# EIS_Sensoren.net
KiCad netlist of a schematic drawn in Altium Designer
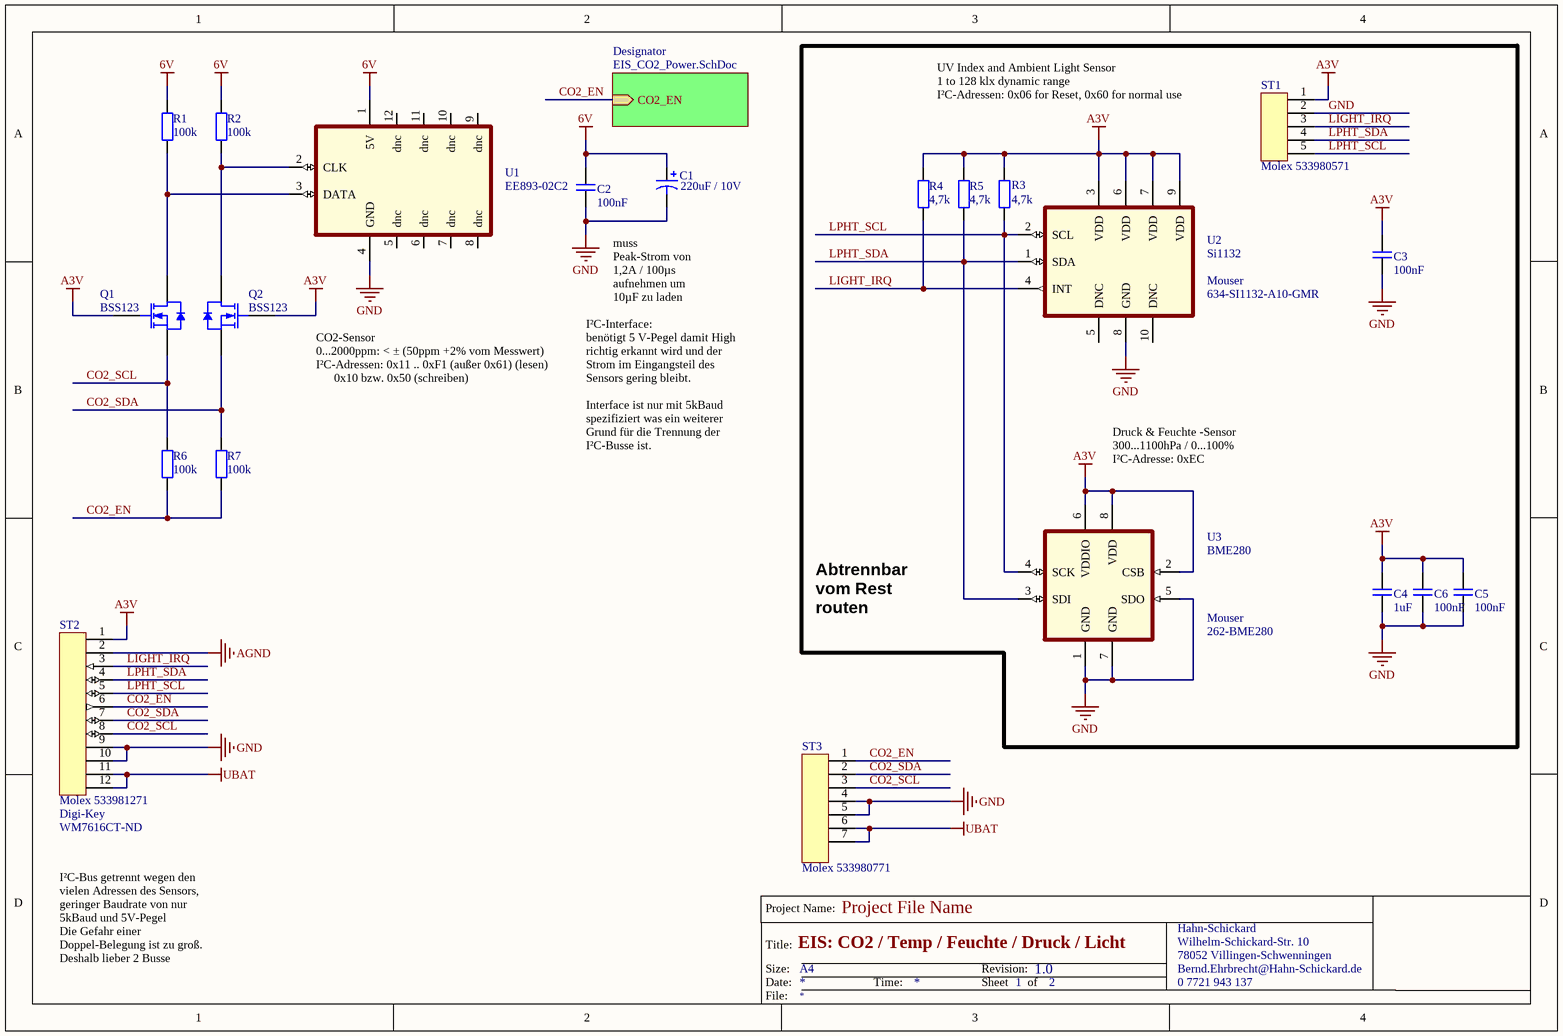
[diagram p0: EIS_Sensoren.SchDoc]

(export (version "E")
  (design (tool "Eeschema 10.0.6"))
  (components
    (comp (ref "C1")
      (value "220uF / 10V")
      (footprint "D")
      (description "Polarized Capacitor (Surface Mount)")
      (fields (field (name "PUBLISHER") "Altium Limited"))
      (libsource (lib "Miscellaneous Devices") (part "Cap Pol3"))
    )
    (comp (ref "C2")
      (value "100nF")
      (footprint "CAPC1608N")
      (libsource (lib "My_Schlib_6_18") (part "Kondensator SMD Keramik"))
    )
    (comp (ref "C3")
      (value "100nF")
      (footprint "CAPC1608N")
      (libsource (lib "My_Schlib_6_18") (part "Kondensator SMD Keramik"))
    )
    (comp (ref "C4")
      (value "1uF")
      (footprint "CAPC3216N")
      (libsource (lib "My_Schlib_6_18") (part "Kondensator SMD Keramik"))
    )
    (comp (ref "C5")
      (value "100nF")
      (footprint "CAPC1608N")
      (libsource (lib "My_Schlib_6_18") (part "Kondensator SMD Keramik"))
    )
    (comp (ref "C6")
      (value "100nF")
      (footprint "CAPC1608N")
      (libsource (lib "My_Schlib_6_18") (part "Kondensator SMD Keramik"))
    )
    (comp (ref "Q1")
      (value "BSS123")
      (footprint "SOT23_N")
      (description "N-channel Enhancement Mode Vertical D-MOSFET")
      (fields (field (name "PUBLISHER") "Altium Limited"))
      (libsource (lib "Philips Discrete MOSFET - Low Power") (part "BSS123"))
    )
    (comp (ref "Q2")
      (value "BSS123")
      (footprint "SOT23_N")
      (description "N-channel Enhancement Mode Vertical D-MOSFET")
      (fields (field (name "PUBLISHER") "Altium Limited"))
      (libsource (lib "Philips Discrete MOSFET - Low Power") (part "BSS123"))
    )
    (comp (ref "R1")
      (value "100k")
      (footprint "RESC1608N")
      (description "RESC1608 (R0603)")
      (fields (field (name "PUBLISHER") "HSG Jürgen Merz"))
      (libsource (lib "MetaSensClampOn_BT") (part "RESC1608 (R0603)"))
    )
    (comp (ref "R2")
      (value "100k")
      (footprint "RESC1608N")
      (description "RESC1608 (R0603)")
      (fields (field (name "PUBLISHER") "HSG Jürgen Merz"))
      (libsource (lib "MetaSensClampOn_BT") (part "RESC1608 (R0603)"))
    )
    (comp (ref "R3")
      (value "4,7k")
      (footprint "RESC1608N")
      (description "RESC1608 (R0603)")
      (fields (field (name "PUBLISHER") "HSG Jürgen Merz"))
      (libsource (lib "MetaSensClampOn_BT") (part "RESC1608 (R0603)"))
    )
    (comp (ref "R4")
      (value "4,7k")
      (footprint "RESC1608N")
      (description "RESC1608 (R0603)")
      (fields (field (name "PUBLISHER") "HSG Jürgen Merz"))
      (libsource (lib "MetaSensClampOn_BT") (part "RESC1608 (R0603)"))
    )
    (comp (ref "R5")
      (value "4,7k")
      (footprint "RESC1608N")
      (description "RESC1608 (R0603)")
      (fields (field (name "PUBLISHER") "HSG Jürgen Merz"))
      (libsource (lib "MetaSensClampOn_BT") (part "RESC1608 (R0603)"))
    )
    (comp (ref "R6")
      (value "100k")
      (footprint "RESC1608N")
      (description "RESC1608 (R0603)")
      (fields (field (name "PUBLISHER") "HSG Jürgen Merz"))
      (libsource (lib "MetaSensClampOn_BT") (part "RESC1608 (R0603)"))
    )
    (comp (ref "R7")
      (value "100k")
      (footprint "RESC1608N")
      (description "RESC1608 (R0603)")
      (fields (field (name "PUBLISHER") "HSG Jürgen Merz"))
      (libsource (lib "MetaSensClampOn_BT") (part "RESC1608 (R0603)"))
    )
    (comp (ref "ST1")
      (value "Molex 533980571")
      (footprint "Molex 533980571")
      (description "MOLEX - 53398-0571 - STIFTLEISTE, SMT, 1.25MM, 5POL")
      (libsource (lib "JM_Elektromechanik") (part "Molex 533980571"))
    )
    (comp (ref "ST2")
      (value "Molex 533981271")
      (footprint "Molex 533981271")
      (description "Molex Pico 12Pol Blade SMD gerade 533980871")
      (fields (field (name "SUPPLIER 1") "Digi-Key") (field (name "SUPPLIER PART NUMBER 1") "WM7616CT-ND"))
      (libsource (lib "JM_Elektromechanik") (part "Molex 533981271"))
    )
    (comp (ref "ST3")
      (value "Molex 533980771")
      (footprint "Molex 533980771")
      (description "Molex Pico 7Pol Blade SMD gerade 533980771")
      (libsource (lib "JM_Elektromechanik") (part "Molex 533980771"))
    )
    (comp (ref "U1")
      (value "EE893-02C2")
      (footprint "EE893")
      (description "CO2-Sensor; I²C-Interface,")
      (libsource (lib "Eis_Lib") (part "EE893-02C2"))
    )
    (comp (ref "U2")
      (value "Si1132")
      (footprint "Si1132")
      (description "UV INDEX AND AMBIENT LIGHT SENSOR IC WITH I2C INTERFACE, QFN 2x2mm")
      (fields
        (field (name "SUPPLIER 1") "Mouser")
        (field (name "SUPPLIER PART NUMBER 1") "634-SI1132-A10-GMR")
      )
      (libsource (lib "Eis_Lib") (part "Si1132"))
    )
    (comp (ref "U3")
      (value "BME280")
      (footprint "BME280")
      (description "Bosch, Druck & Feuchte-Sensor, I2C / SPI")
      (fields (field (name "SUPPLIER 1") "Mouser") (field (name "SUPPLIER PART NUMBER 1") "262-BME280"))
      (libsource (lib "Eis_Lib") (part "BME280"))
    )
  )
  (nets
    (net (code "1") (name "/CO2_EN") (class "Default")
      (node (ref "R6") (pin "1") (pinfunction "1_1") (pintype "passive"))
      (node (ref "R7") (pin "1") (pinfunction "1_1") (pintype "passive"))
      (node (ref "ST2") (pin "6") (pinfunction "6_6") (pintype "output"))
      (node (ref "ST3") (pin "1") (pinfunction "1_1") (pintype "passive"))
    )
    (net (code "2") (name "/CO2_SCL") (class "Default")
      (node (ref "Q1") (pin "2") (pinfunction "S_2") (pintype "passive"))
      (node (ref "R6") (pin "2") (pinfunction "2_2") (pintype "passive"))
      (node (ref "ST2") (pin "8") (pinfunction "8_8") (pintype "bidirectional"))
      (node (ref "ST3") (pin "3") (pinfunction "3_3") (pintype "passive"))
    )
    (net (code "3") (name "/CO2_SDA") (class "Default")
      (node (ref "Q2") (pin "2") (pinfunction "S_2") (pintype "passive"))
      (node (ref "R7") (pin "2") (pinfunction "2_2") (pintype "passive"))
      (node (ref "ST2") (pin "7") (pinfunction "7_7") (pintype "bidirectional"))
      (node (ref "ST3") (pin "2") (pinfunction "2_2") (pintype "passive"))
    )
    (net (code "4") (name "/LIGHT_IRQ") (class "Default")
      (node (ref "R4") (pin "1") (pinfunction "1_1") (pintype "passive"))
      (node (ref "ST1") (pin "3") (pinfunction "3_3") (pintype "passive"))
      (node (ref "ST2") (pin "3") (pinfunction "3_3") (pintype "input"))
      (node (ref "U2") (pin "4") (pinfunction "INT_4") (pintype "output"))
    )
    (net (code "5") (name "/LPHT_SCL") (class "Default")
      (node (ref "R3") (pin "1") (pinfunction "1_1") (pintype "passive"))
      (node (ref "ST1") (pin "5") (pinfunction "5_5") (pintype "passive"))
      (node (ref "ST2") (pin "5") (pinfunction "5_5") (pintype "bidirectional"))
      (node (ref "U2") (pin "2") (pinfunction "SCL_2") (pintype "bidirectional"))
      (node (ref "U3") (pin "4") (pinfunction "SCK_4") (pintype "bidirectional"))
    )
    (net (code "6") (name "/LPHT_SDA") (class "Default")
      (node (ref "R5") (pin "1") (pinfunction "1_1") (pintype "passive"))
      (node (ref "ST1") (pin "4") (pinfunction "4_4") (pintype "passive"))
      (node (ref "ST2") (pin "4") (pinfunction "4_4") (pintype "bidirectional"))
      (node (ref "U2") (pin "1") (pinfunction "SDA_1") (pintype "bidirectional"))
      (node (ref "U3") (pin "3") (pinfunction "SDI_3") (pintype "bidirectional"))
    )
    (net (code "7") (name "6V") (class "Default")
      (node (ref "C1") (pin "1") (pinfunction "1_1") (pintype "passive"))
      (node (ref "C2") (pin "1") (pinfunction "1_1") (pintype "passive"))
      (node (ref "R1") (pin "2") (pinfunction "2_2") (pintype "passive"))
      (node (ref "R2") (pin "2") (pinfunction "2_2") (pintype "passive"))
      (node (ref "U1") (pin "1") (pinfunction "5V_1") (pintype "power_in"))
    )
    (net (code "8") (name "A3V") (class "Default")
      (node (ref "C3") (pin "1") (pinfunction "1_1") (pintype "passive"))
      (node (ref "C4") (pin "1") (pinfunction "1_1") (pintype "passive"))
      (node (ref "C5") (pin "1") (pinfunction "1_1") (pintype "passive"))
      (node (ref "C6") (pin "1") (pinfunction "1_1") (pintype "passive"))
      (node (ref "Q1") (pin "1") (pinfunction "G_1") (pintype "passive"))
      (node (ref "Q2") (pin "1") (pinfunction "G_1") (pintype "passive"))
      (node (ref "R3") (pin "2") (pinfunction "2_2") (pintype "passive"))
      (node (ref "R4") (pin "2") (pinfunction "2_2") (pintype "passive"))
      (node (ref "R5") (pin "2") (pinfunction "2_2") (pintype "passive"))
      (node (ref "ST1") (pin "1") (pinfunction "1_1") (pintype "passive"))
      (node (ref "ST2") (pin "1") (pinfunction "1_1") (pintype "passive"))
      (node (ref "U2") (pin "3") (pinfunction "VDD_3") (pintype "power_in"))
      (node (ref "U2") (pin "6") (pinfunction "VDD_6") (pintype "power_in"))
      (node (ref "U2") (pin "7") (pinfunction "VDD_7") (pintype "power_in"))
      (node (ref "U2") (pin "9") (pinfunction "VDD_9") (pintype "power_in"))
      (node (ref "U3") (pin "2") (pinfunction "CSB_2") (pintype "input"))
      (node (ref "U3") (pin "6") (pinfunction "VDDIO_6") (pintype "power_in"))
      (node (ref "U3") (pin "8") (pinfunction "VDD_8") (pintype "power_in"))
    )
    (net (code "9") (name "AGND") (class "Default")
      (node (ref "ST2") (pin "2") (pinfunction "2_2") (pintype "passive"))
    )
    (net (code "10") (name "GND") (class "Default")
      (node (ref "C1") (pin "2") (pinfunction "2_2") (pintype "passive"))
      (node (ref "C2") (pin "2") (pinfunction "2_2") (pintype "passive"))
      (node (ref "C3") (pin "2") (pinfunction "2_2") (pintype "passive"))
      (node (ref "C4") (pin "2") (pinfunction "2_2") (pintype "passive"))
      (node (ref "C5") (pin "2") (pinfunction "2_2") (pintype "passive"))
      (node (ref "C6") (pin "2") (pinfunction "2_2") (pintype "passive"))
      (node (ref "ST1") (pin "2") (pinfunction "2_2") (pintype "passive"))
      (node (ref "ST2") (pin "10") (pinfunction "10_10") (pintype "passive"))
      (node (ref "ST2") (pin "9") (pinfunction "9_9") (pintype "passive"))
      (node (ref "ST3") (pin "4") (pinfunction "4_4") (pintype "passive"))
      (node (ref "ST3") (pin "5") (pinfunction "5_5") (pintype "passive"))
      (node (ref "U1") (pin "4") (pinfunction "GND_4") (pintype "power_in"))
      (node (ref "U2") (pin "8") (pinfunction "GND_8") (pintype "power_in"))
      (node (ref "U3") (pin "1") (pinfunction "GND_1") (pintype "power_in"))
      (node (ref "U3") (pin "5") (pinfunction "SDO_5") (pintype "input"))
      (node (ref "U3") (pin "7") (pinfunction "GND_7") (pintype "power_in"))
    )
    (net (code "11") (name "Net-(Q1-D)") (class "Default")
      (node (ref "Q1") (pin "3") (pinfunction "D_3") (pintype "passive"))
      (node (ref "R1") (pin "1") (pinfunction "1_1") (pintype "passive"))
      (node (ref "U1") (pin "3") (pinfunction "DATA_3") (pintype "bidirectional"))
    )
    (net (code "12") (name "Net-(Q2-D)") (class "Default")
      (node (ref "Q2") (pin "3") (pinfunction "D_3") (pintype "passive"))
      (node (ref "R2") (pin "1") (pinfunction "1_1") (pintype "passive"))
      (node (ref "U1") (pin "2") (pinfunction "CLK_2") (pintype "bidirectional"))
    )
    (net (code "13") (name "UBAT") (class "Default")
      (node (ref "ST2") (pin "11") (pinfunction "11_11") (pintype "passive"))
      (node (ref "ST2") (pin "12") (pinfunction "12_12") (pintype "passive"))
      (node (ref "ST3") (pin "6") (pinfunction "6_6") (pintype "passive"))
      (node (ref "ST3") (pin "7") (pinfunction "7_7") (pintype "passive"))
    )
    (net (code "14") (name "unconnected-(ST1-Pad6)") (class "Default")
      (node (ref "ST1") (pin "6") (pinfunction "6_6") (pintype "passive"))
    )
    (net (code "15") (name "unconnected-(ST1-Pad7)") (class "Default")
      (node (ref "ST1") (pin "7") (pinfunction "7_7") (pintype "passive"))
    )
    (net (code "16") (name "unconnected-(ST2-Pad13)") (class "Default")
      (node (ref "ST2") (pin "13") (pinfunction "13_13") (pintype "passive"))
    )
    (net (code "17") (name "unconnected-(ST2-Pad14)") (class "Default")
      (node (ref "ST2") (pin "14") (pinfunction "14_14") (pintype "passive"))
    )
    (net (code "18") (name "unconnected-(ST3-Pad8)") (class "Default")
      (node (ref "ST3") (pin "8") (pinfunction "8_8") (pintype "passive"))
    )
    (net (code "19") (name "unconnected-(ST3-Pad9)") (class "Default")
      (node (ref "ST3") (pin "9") (pinfunction "9_9") (pintype "passive"))
    )
    (net (code "20") (name "unconnected-(U1-dnc-Pad5)") (class "Default")
      (node (ref "U1") (pin "5") (pinfunction "dnc_5") (pintype "passive"))
    )
    (net (code "21") (name "unconnected-(U1-dnc-Pad6)") (class "Default")
      (node (ref "U1") (pin "6") (pinfunction "dnc_6") (pintype "passive"))
    )
    (net (code "22") (name "unconnected-(U1-dnc-Pad7)") (class "Default")
      (node (ref "U1") (pin "7") (pinfunction "dnc_7") (pintype "passive"))
    )
    (net (code "23") (name "unconnected-(U1-dnc-Pad8)") (class "Default")
      (node (ref "U1") (pin "8") (pinfunction "dnc_8") (pintype "passive"))
    )
    (net (code "24") (name "unconnected-(U1-dnc-Pad9)") (class "Default")
      (node (ref "U1") (pin "9") (pinfunction "dnc_9") (pintype "passive"))
    )
    (net (code "25") (name "unconnected-(U1-dnc-Pad10)") (class "Default")
      (node (ref "U1") (pin "10") (pinfunction "dnc_10") (pintype "passive"))
    )
    (net (code "26") (name "unconnected-(U1-dnc-Pad11)") (class "Default")
      (node (ref "U1") (pin "11") (pinfunction "dnc_11") (pintype "passive"))
    )
    (net (code "27") (name "unconnected-(U1-dnc-Pad12)") (class "Default")
      (node (ref "U1") (pin "12") (pinfunction "dnc_12") (pintype "passive"))
    )
    (net (code "28") (name "unconnected-(U2-DNC-Pad5)") (class "Default")
      (node (ref "U2") (pin "5") (pinfunction "DNC_5") (pintype "passive"))
    )
    (net (code "29") (name "unconnected-(U2-DNC-Pad10)") (class "Default")
      (node (ref "U2") (pin "10") (pinfunction "DNC_10") (pintype "passive"))
    )
  )
)
